# Haptic_Motor_Driver_DRV2605L.net
KiCad netlist of a schematic drawn in EAGLE
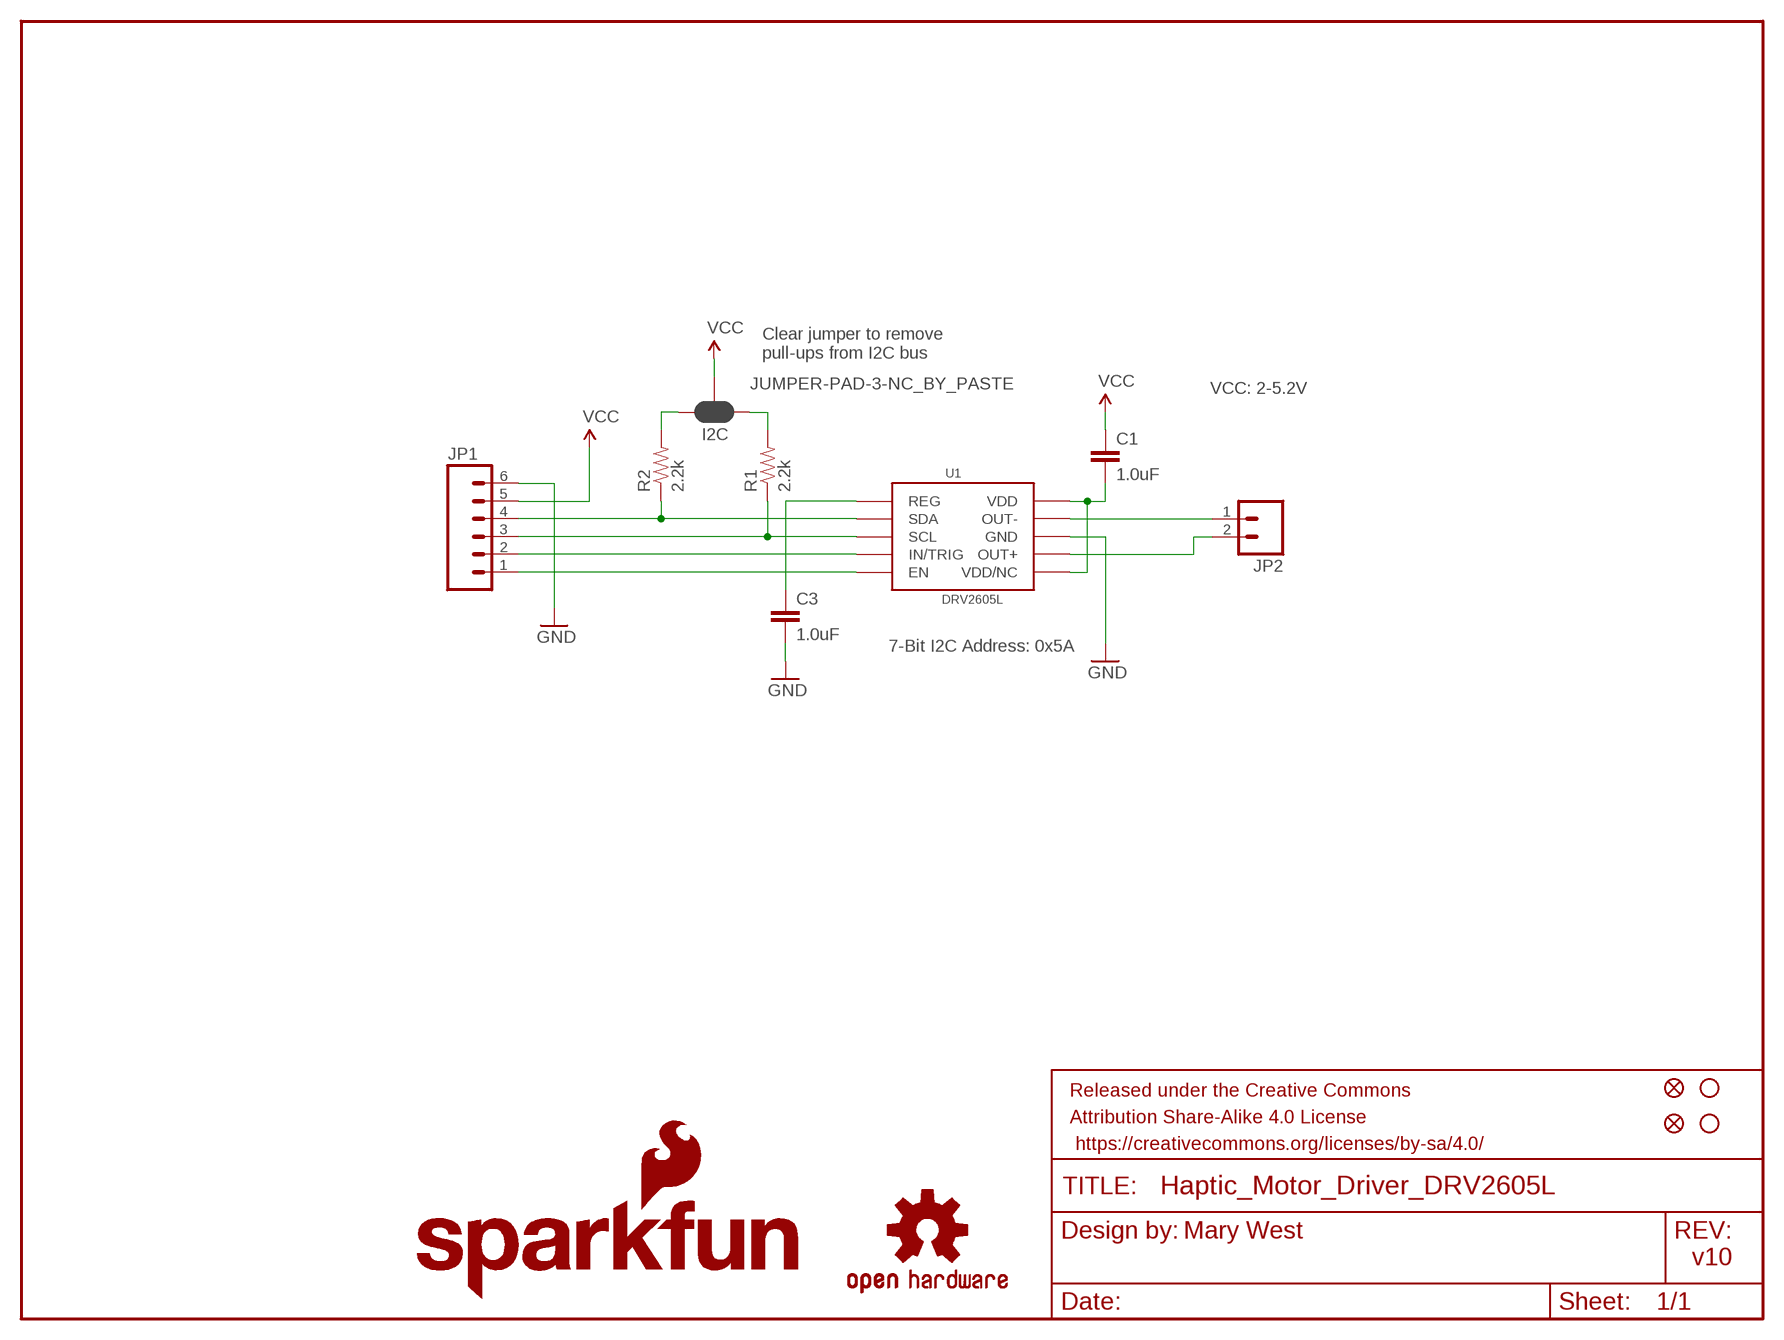
[diagram p0: schematic, sheet 1]

(export (version "E")
  (design (tool "Eeschema 10.0.6"))
  (components
    (comp (ref "C1")
      (value "1.0uF")
      (footprint "eagle-import:0402-CAP")
      (libsource (lib "eagle-import") (part "1.0UF-16V-10%(0402)"))
    )
    (comp (ref "C3")
      (value "1.0uF")
      (footprint "eagle-import:0402-CAP")
      (libsource (lib "eagle-import") (part "1.0UF-16V-10%(0402)"))
    )
    (comp (ref "FID1")
      (value "FIDUCIAL1X2")
      (footprint "eagle-import:FIDUCIAL-1X2")
      (libsource (lib "eagle-import") (part "FIDUCIAL1X2"))
    )
    (comp (ref "FID2")
      (value "FIDUCIAL1X2")
      (footprint "eagle-import:FIDUCIAL-1X2")
      (libsource (lib "eagle-import") (part "FIDUCIAL1X2"))
    )
    (comp (ref "FRAME2")
      (value "FRAME-LETTER")
      (footprint "eagle-import:CREATIVE_COMMONS")
      (libsource (lib "eagle-import") (part "FRAME-LETTER"))
    )
    (comp (ref "I2C")
      (value "JUMPER-PAD-3-NC_BY_PASTE")
      (footprint "eagle-import:PAD-JUMPER-3-NC_BY_PASTE_YES_SILK_FULL_BOX")
      (libsource (lib "eagle-import") (part "JUMPER-PAD-3-NC_BY_PASTE"))
    )
    (comp (ref "JP1")
      (value "M06SILK_FEMALE_PTH")
      (footprint "eagle-import:1X06")
      (libsource (lib "eagle-import") (part "M06SILK_FEMALE_PTH"))
    )
    (comp (ref "JP2")
      (value "M02PTH")
      (footprint "eagle-import:1X02")
      (libsource (lib "eagle-import") (part "M02PTH"))
    )
    (comp (ref "LOGO2")
      (value "OSHW-LOGOS")
      (footprint "eagle-import:OSHW-LOGO-S")
      (libsource (lib "eagle-import") (part "OSHW-LOGOS"))
    )
    (comp (ref "LOGO4")
      (value "SFE_LOGO_NAME_FLAME.1_INCH")
      (footprint "eagle-import:SFE_LOGO_NAME_FLAME_.1")
      (libsource (lib "eagle-import") (part "SFE_LOGO_NAME_FLAME.1_INCH"))
    )
    (comp (ref "R1")
      (value "2.2k")
      (footprint "eagle-import:0603-RES")
      (libsource (lib "eagle-import") (part "2.2KOHM-1/10W-1%(0603)"))
    )
    (comp (ref "R2")
      (value "2.2k")
      (footprint "eagle-import:0603-RES")
      (libsource (lib "eagle-import") (part "2.2KOHM-1/10W-1%(0603)"))
    )
    (comp (ref "STANDOFF1")
      (value "STAND-OFF")
      (footprint "eagle-import:STAND-OFF")
      (libsource (lib "eagle-import") (part "STAND-OFF"))
    )
    (comp (ref "STANDOFF4")
      (value "STAND-OFF")
      (footprint "eagle-import:STAND-OFF")
      (libsource (lib "eagle-import") (part "STAND-OFF"))
    )
    (comp (ref "U1")
      (value "DRV2605L")
      (footprint "eagle-import:VSSOP-10")
      (libsource (lib "eagle-import") (part "DRV2605L"))
    )
  )
  (nets
    (net (code "1") (name "GND") (class "Default")
      (node (ref "C3") (pin "2") (pinfunction "2_2") (pintype "passive"))
      (node (ref "JP1") (pin "6") (pinfunction "6_6") (pintype "passive"))
      (node (ref "U1") (pin "P$8") (pinfunction "GND_P$8") (pintype "bidirectional"))
    )
    (net (code "2") (name "Net-(I2C-Pad1)") (class "Default")
      (node (ref "I2C") (pin "1") (pinfunction "1_1") (pintype "passive"))
      (node (ref "R1") (pin "2") (pinfunction "2_2") (pintype "passive"))
    )
    (net (code "3") (name "Net-(I2C-Pad3)") (class "Default")
      (node (ref "I2C") (pin "3") (pinfunction "3_3") (pintype "passive"))
      (node (ref "R2") (pin "2") (pinfunction "2_2") (pintype "passive"))
    )
    (net (code "4") (name "Net-(U1-EN)") (class "Default")
      (node (ref "JP1") (pin "1") (pinfunction "1_1") (pintype "passive"))
      (node (ref "U1") (pin "P$5") (pinfunction "EN_P$5") (pintype "bidirectional"))
    )
    (net (code "5") (name "Net-(U1-IN{slash}TRIG)") (class "Default")
      (node (ref "JP1") (pin "2") (pinfunction "2_2") (pintype "passive"))
      (node (ref "U1") (pin "P$4") (pinfunction "IN/TRIG_P$4") (pintype "bidirectional"))
    )
    (net (code "6") (name "Net-(U1-OUT+)") (class "Default")
      (node (ref "JP2") (pin "2") (pinfunction "2_2") (pintype "passive"))
      (node (ref "U1") (pin "P$7") (pinfunction "OUT+_P$7") (pintype "bidirectional"))
    )
    (net (code "7") (name "Net-(U1-OUT-)") (class "Default")
      (node (ref "JP2") (pin "1") (pinfunction "1_1") (pintype "passive"))
      (node (ref "U1") (pin "P$9") (pinfunction "OUT-_P$9") (pintype "bidirectional"))
    )
    (net (code "8") (name "Net-(U1-REG)") (class "Default")
      (node (ref "C3") (pin "1") (pinfunction "1_1") (pintype "passive"))
      (node (ref "U1") (pin "P$1") (pinfunction "REG_P$1") (pintype "bidirectional"))
    )
    (net (code "9") (name "Net-(U1-SCL)") (class "Default")
      (node (ref "JP1") (pin "3") (pinfunction "3_3") (pintype "passive"))
      (node (ref "R1") (pin "1") (pinfunction "1_1") (pintype "passive"))
      (node (ref "U1") (pin "P$2") (pinfunction "SCL_P$2") (pintype "bidirectional"))
    )
    (net (code "10") (name "Net-(U1-SDA)") (class "Default")
      (node (ref "JP1") (pin "4") (pinfunction "4_4") (pintype "passive"))
      (node (ref "R2") (pin "1") (pinfunction "1_1") (pintype "passive"))
      (node (ref "U1") (pin "P$3") (pinfunction "SDA_P$3") (pintype "bidirectional"))
    )
    (net (code "11") (name "Net-(U1-VDD)") (class "Default")
      (node (ref "C1") (pin "2") (pinfunction "2_2") (pintype "passive"))
      (node (ref "U1") (pin "P$10") (pinfunction "VDD_P$10") (pintype "bidirectional"))
      (node (ref "U1") (pin "P$6") (pinfunction "VDD/NC_P$6") (pintype "bidirectional"))
    )
    (net (code "12") (name "VCC") (class "Default")
      (node (ref "C1") (pin "1") (pinfunction "1_1") (pintype "passive"))
      (node (ref "I2C") (pin "2") (pinfunction "2_2") (pintype "passive"))
      (node (ref "JP1") (pin "5") (pinfunction "5_5") (pintype "passive"))
    )
  )
)
